# polarshield3_0f.net
KiCad netlist of a schematic drawn in EAGLE
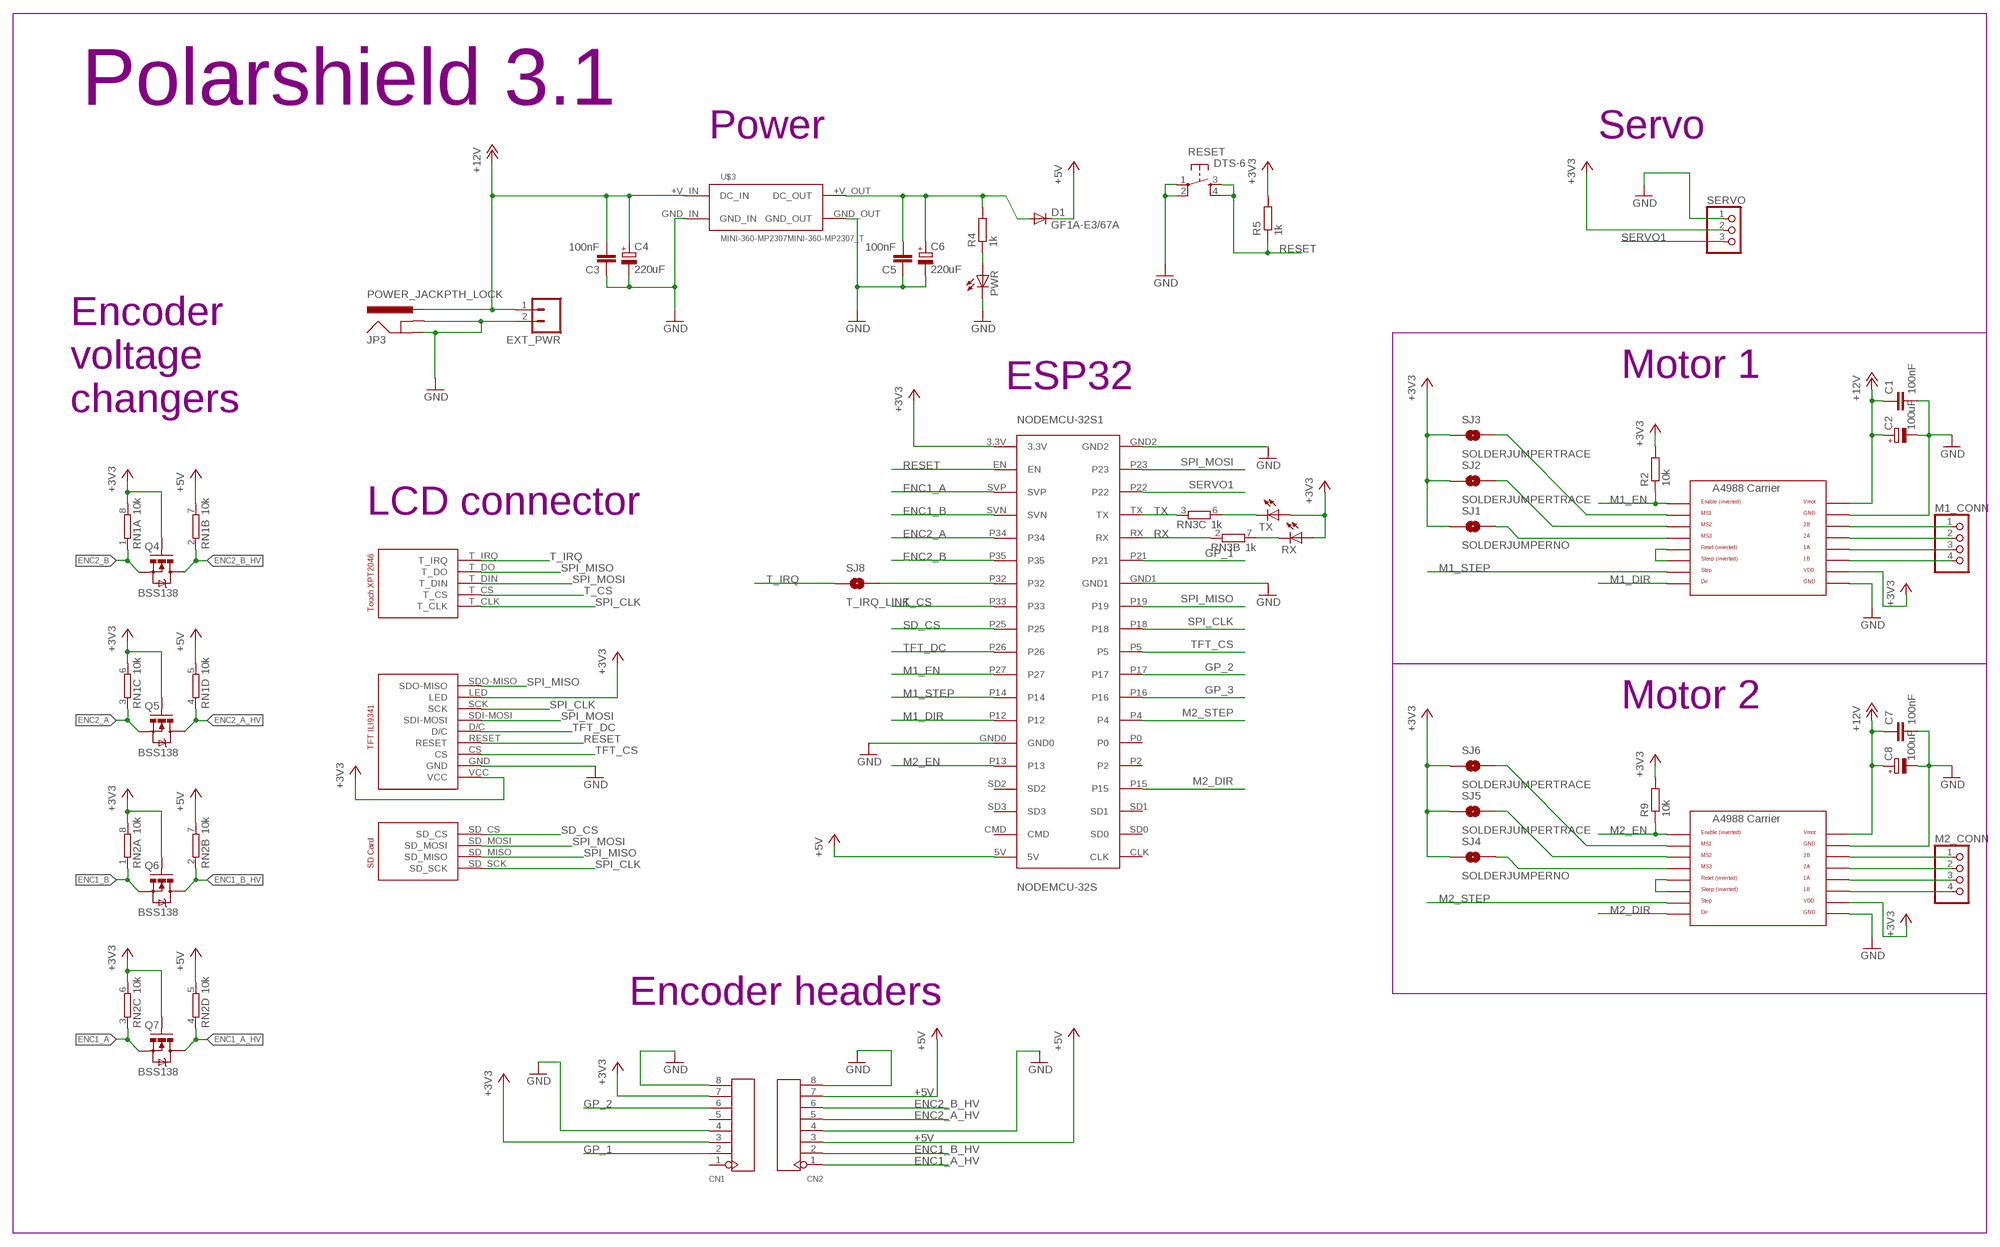
[diagram p0: schematic, sheet 1]

(export (version "E")
  (design (tool "Eeschema 10.0.6"))
  (components
    (comp (ref "C1")
      (value "100nF")
      (footprint "eagle-import:C0805")
      (libsource (lib "eagle-import") (part "C-EUC0805"))
    )
    (comp (ref "C2")
      (value "100uF")
      (footprint "eagle-import:153CLV-0605")
      (libsource (lib "eagle-import") (part "CPOL-EU153CLV-0605"))
    )
    (comp (ref "C3")
      (value "100nF")
      (footprint "eagle-import:C0805")
      (libsource (lib "eagle-import") (part "C-EUC0805"))
    )
    (comp (ref "C4")
      (value "220uF")
      (footprint "eagle-import:153CLV-0605")
      (libsource (lib "eagle-import") (part "CPOL-EU153CLV-0605"))
    )
    (comp (ref "C5")
      (value "100nF")
      (footprint "eagle-import:C0805")
      (libsource (lib "eagle-import") (part "C-EUC0805"))
    )
    (comp (ref "C6")
      (value "220uF")
      (footprint "eagle-import:153CLV-0605")
      (libsource (lib "eagle-import") (part "CPOL-EU153CLV-0605"))
    )
    (comp (ref "C7")
      (value "100nF")
      (footprint "eagle-import:C0805")
      (libsource (lib "eagle-import") (part "C-EUC0805"))
    )
    (comp (ref "C8")
      (value "100uF")
      (footprint "eagle-import:153CLV-0605")
      (libsource (lib "eagle-import") (part "CPOL-EU153CLV-0605"))
    )
    (comp (ref "CN1")
      (value "DIP-BLACK-FEMALE-HEADER-VERT(8P-2.54)")
      (footprint "eagle-import:H8-2.54")
      (fields (field (name "MPN") "F185-1108A1BSYC1"))
      (libsource (lib "eagle-import") (part "DIP-BLACK-FEMALE-HEADER-VERT(8P-2.54)"))
    )
    (comp (ref "CN2")
      (value "DIP-BLACK-FEMALE-HEADER-VERT(8P-2.54)")
      (footprint "eagle-import:H8-2.54")
      (fields (field (name "MPN") "F185-1108A1BSYC1"))
      (libsource (lib "eagle-import") (part "DIP-BLACK-FEMALE-HEADER-VERT(8P-2.54)"))
    )
    (comp (ref "D1")
      (value "GF1A-E3/67A")
      (footprint "eagle-import:DO214BA")
      (libsource (lib "eagle-import") (part "DIODE-DO214BA"))
    )
    (comp (ref "EXT_PWR")
      (value "M02PTH")
      (footprint "eagle-import:1X02")
      (libsource (lib "eagle-import") (part "M02PTH"))
    )
    (comp (ref "JP3")
      (value "POWER_JACKPTH_LOCK")
      (footprint "eagle-import:POWER_JACK_PTH_LOCK")
      (libsource (lib "eagle-import") (part "POWER_JACKPTH_LOCK"))
    )
    (comp (ref "M1_CONN")
      (value "PINHD-1X4/90")
      (footprint "eagle-import:1X04_90")
      (libsource (lib "eagle-import") (part "PINHD-1X4/90"))
    )
    (comp (ref "M2_CONN")
      (value "PINHD-1X4/90")
      (footprint "eagle-import:1X04_90")
      (libsource (lib "eagle-import") (part "PINHD-1X4/90"))
    )
    (comp (ref "MOTOR_1")
      (value "A4988BREAKOUT")
      (footprint "eagle-import:A4988BREAKOUT")
      (libsource (lib "eagle-import") (part "A4988BREAKOUT"))
    )
    (comp (ref "MOTOR_2")
      (value "A4988BREAKOUT")
      (footprint "eagle-import:A4988BREAKOUT")
      (libsource (lib "eagle-import") (part "A4988BREAKOUT"))
    )
    (comp (ref "NODEMCU-32S1")
      (value "NODEMCU-32S")
      (footprint "eagle-import:NODEMCU-32S")
      (libsource (lib "eagle-import") (part "NODEMCU-32S"))
    )
    (comp (ref "PWR")
      (value "LEDCHIPLED_0805")
      (footprint "eagle-import:CHIPLED_0805")
      (libsource (lib "eagle-import") (part "LEDCHIPLED_0805"))
    )
    (comp (ref "Q4")
      (value "BSS138")
      (footprint "eagle-import:SOT23-3")
      (libsource (lib "eagle-import") (part "MOSFET-NCHANNELSMD"))
    )
    (comp (ref "Q5")
      (value "BSS138")
      (footprint "eagle-import:SOT23-3")
      (libsource (lib "eagle-import") (part "MOSFET-NCHANNELSMD"))
    )
    (comp (ref "Q6")
      (value "BSS138")
      (footprint "eagle-import:SOT23-3")
      (libsource (lib "eagle-import") (part "MOSFET-NCHANNELSMD"))
    )
    (comp (ref "Q7")
      (value "BSS138")
      (footprint "eagle-import:SOT23-3")
      (libsource (lib "eagle-import") (part "MOSFET-NCHANNELSMD"))
    )
    (comp (ref "R2")
      (value "10k")
      (footprint "eagle-import:M0805")
      (libsource (lib "eagle-import") (part "R-EU_M0805"))
    )
    (comp (ref "R4")
      (value "1k")
      (footprint "eagle-import:M0805")
      (libsource (lib "eagle-import") (part "R-EU_M0805"))
    )
    (comp (ref "R5")
      (value "1k")
      (footprint "eagle-import:M0805")
      (libsource (lib "eagle-import") (part "R-EU_M0805"))
    )
    (comp (ref "R9")
      (value "10k")
      (footprint "eagle-import:M0805")
      (libsource (lib "eagle-import") (part "R-EU_M0805"))
    )
    (comp (ref "RESET")
      (value "DTS-6")
      (footprint "eagle-import:DTS-6")
      (libsource (lib "eagle-import") (part "DTS-6"))
    )
    (comp (ref "RN1")
      (value "10k")
      (footprint "eagle-import:EXB38V")
      (libsource (lib "eagle-import") (part "4R-NEXB38V"))
    )
    (comp (ref "RN2")
      (value "10k")
      (footprint "eagle-import:EXB38V")
      (libsource (lib "eagle-import") (part "4R-NEXB38V"))
    )
    (comp (ref "RN3")
      (value "1k")
      (footprint "eagle-import:EXB38V")
      (libsource (lib "eagle-import") (part "4R-NEXB38V"))
    )
    (comp (ref "RX")
      (value "LEDCHIPLED_0805")
      (footprint "eagle-import:CHIPLED_0805")
      (libsource (lib "eagle-import") (part "LEDCHIPLED_0805"))
    )
    (comp (ref "SERVO")
      (value "PINHD-1X3/90")
      (footprint "eagle-import:1X03_90")
      (libsource (lib "eagle-import") (part "PINHD-1X3/90"))
    )
    (comp (ref "SJ1")
      (value "SOLDERJUMPERNO")
      (footprint "eagle-import:SJ_2S-NO")
      (libsource (lib "eagle-import") (part "polargraph3_SOLDERJUMPERNO"))
    )
    (comp (ref "SJ2")
      (value "SOLDERJUMPERTRACE")
      (footprint "eagle-import:SJ_2S-TRACE")
      (libsource (lib "eagle-import") (part "polargraph3_SOLDERJUMPERTRACE"))
    )
    (comp (ref "SJ3")
      (value "SOLDERJUMPERTRACE")
      (footprint "eagle-import:SJ_2S-TRACE")
      (libsource (lib "eagle-import") (part "polargraph3_SOLDERJUMPERTRACE"))
    )
    (comp (ref "SJ4")
      (value "SOLDERJUMPERNO")
      (footprint "eagle-import:SJ_2S-NO")
      (libsource (lib "eagle-import") (part "polargraph3_SOLDERJUMPERNO"))
    )
    (comp (ref "SJ5")
      (value "SOLDERJUMPERTRACE")
      (footprint "eagle-import:SJ_2S-TRACE")
      (libsource (lib "eagle-import") (part "polargraph3_SOLDERJUMPERTRACE"))
    )
    (comp (ref "SJ6")
      (value "SOLDERJUMPERTRACE")
      (footprint "eagle-import:SJ_2S-TRACE")
      (libsource (lib "eagle-import") (part "polargraph3_SOLDERJUMPERTRACE"))
    )
    (comp (ref "SJ8")
      (value "T_IRQ_LINK")
      (footprint "eagle-import:SJ_2S-NO")
      (libsource (lib "eagle-import") (part "SOLDERJUMPERNO"))
    )
    (comp (ref "TX")
      (value "LEDCHIPLED_0805")
      (footprint "eagle-import:CHIPLED_0805")
      (libsource (lib "eagle-import") (part "LEDCHIPLED_0805"))
    )
    (comp (ref "U$2")
      (value "2.4_TFT_SPI_TOUCH_SD")
      (footprint "eagle-import:2.4_TFT_SPI_TOUCH_SD")
      (libsource (lib "eagle-import") (part "2.4_TFT_SPI_TOUCH_SD"))
    )
    (comp (ref "U$3")
      (value "MINI-360-MP2307MINI-360-MP2307_T")
      (footprint "eagle-import:MINI-360-MP2307")
      (libsource (lib "eagle-import") (part "MINI-360-MP2307MINI-360-MP2307_T"))
    )
  )
  (nets
    (net (code "1") (name "+3V3") (class "Default")
      (node (ref "CN1") (pin "3") (pinfunction "3_3") (pintype "bidirectional"))
      (node (ref "CN1") (pin "7") (pinfunction "7_7") (pintype "bidirectional"))
      (node (ref "MOTOR_1") (pin "VDD") (pinfunction "VDD_VDD") (pintype "power_in"))
      (node (ref "MOTOR_2") (pin "VDD") (pinfunction "VDD_VDD") (pintype "power_in"))
      (node (ref "NODEMCU-32S1") (pin "3.3V") (pinfunction "3.3V_3.3V") (pintype "bidirectional"))
      (node (ref "Q4") (pin "1") (pinfunction "G_1") (pintype "passive"))
      (node (ref "Q5") (pin "1") (pinfunction "G_1") (pintype "passive"))
      (node (ref "Q6") (pin "1") (pinfunction "G_1") (pintype "passive"))
      (node (ref "Q7") (pin "1") (pinfunction "G_1") (pintype "passive"))
      (node (ref "R2") (pin "2") (pinfunction "2_2") (pintype "passive"))
      (node (ref "R5") (pin "2") (pinfunction "2_2") (pintype "passive"))
      (node (ref "R9") (pin "2") (pinfunction "2_2") (pintype "passive"))
      (node (ref "RN1") (pin "6") (pinfunction "2_6") (pintype "passive"))
      (node (ref "RN1") (pin "8") (pinfunction "2_8") (pintype "passive"))
      (node (ref "RN2") (pin "6") (pinfunction "2_6") (pintype "passive"))
      (node (ref "RN2") (pin "8") (pinfunction "2_8") (pintype "passive"))
      (node (ref "RX") (pin "A") (pinfunction "A_A") (pintype "passive"))
      (node (ref "SERVO") (pin "2") (pinfunction "2_2") (pintype "passive"))
      (node (ref "SJ1") (pin "1") (pinfunction "1_1") (pintype "passive"))
      (node (ref "SJ2") (pin "1") (pinfunction "1_1") (pintype "passive"))
      (node (ref "SJ3") (pin "1") (pinfunction "1_1") (pintype "passive"))
      (node (ref "SJ4") (pin "1") (pinfunction "1_1") (pintype "passive"))
      (node (ref "SJ5") (pin "1") (pinfunction "1_1") (pintype "passive"))
      (node (ref "SJ6") (pin "1") (pinfunction "1_1") (pintype "passive"))
      (node (ref "TX") (pin "A") (pinfunction "A_A") (pintype "passive"))
      (node (ref "U$2") (pin "LED") (pinfunction "LED_LED") (pintype "bidirectional"))
      (node (ref "U$2") (pin "VCC") (pinfunction "VCC_VCC") (pintype "bidirectional"))
    )
    (net (code "2") (name "+5V") (class "Default")
      (node (ref "CN2") (pin "3") (pinfunction "3_3") (pintype "bidirectional"))
      (node (ref "CN2") (pin "7") (pinfunction "7_7") (pintype "bidirectional"))
      (node (ref "D1") (pin "C") (pinfunction "C_C") (pintype "passive"))
      (node (ref "NODEMCU-32S1") (pin "5V") (pinfunction "5V_5V") (pintype "bidirectional"))
      (node (ref "RN1") (pin "5") (pinfunction "2_5") (pintype "passive"))
      (node (ref "RN1") (pin "7") (pinfunction "2_7") (pintype "passive"))
      (node (ref "RN2") (pin "5") (pinfunction "2_5") (pintype "passive"))
      (node (ref "RN2") (pin "7") (pinfunction "2_7") (pintype "passive"))
    )
    (net (code "3") (name "+12V") (class "Default")
      (node (ref "C1") (pin "1") (pinfunction "1_1") (pintype "passive"))
      (node (ref "C2") (pin "+") (pinfunction "+_+") (pintype "passive"))
      (node (ref "C3") (pin "2") (pinfunction "2_2") (pintype "passive"))
      (node (ref "C4") (pin "+") (pinfunction "+_+") (pintype "passive"))
      (node (ref "C7") (pin "1") (pinfunction "1_1") (pintype "passive"))
      (node (ref "C8") (pin "+") (pinfunction "+_+") (pintype "passive"))
      (node (ref "EXT_PWR") (pin "1") (pinfunction "1_1") (pintype "passive"))
      (node (ref "JP3") (pin "PWR") (pinfunction "PWR_PWR") (pintype "bidirectional"))
      (node (ref "MOTOR_1") (pin "VMOT") (pinfunction "VMOT_VMOT") (pintype "power_in"))
      (node (ref "MOTOR_2") (pin "VMOT") (pinfunction "VMOT_VMOT") (pintype "power_in"))
      (node (ref "U$3") (pin "+V_IN") (pinfunction "DC_IN_+V_IN") (pintype "bidirectional"))
    )
    (net (code "4") (name "/GP_1") (class "Default")
      (node (ref "CN1") (pin "2") (pinfunction "2_2") (pintype "bidirectional"))
      (node (ref "NODEMCU-32S1") (pin "P21") (pinfunction "P21_P21") (pintype "bidirectional"))
    )
    (net (code "5") (name "/GP_2") (class "Default")
      (node (ref "CN1") (pin "6") (pinfunction "6_6") (pintype "bidirectional"))
      (node (ref "NODEMCU-32S1") (pin "P17") (pinfunction "P17_P17") (pintype "bidirectional"))
    )
    (net (code "6") (name "/GP_3") (class "Default")
      (node (ref "NODEMCU-32S1") (pin "P16") (pinfunction "P16_P16") (pintype "bidirectional"))
    )
    (net (code "7") (name "/M1_DIR") (class "Default")
      (node (ref "MOTOR_1") (pin "DIR") (pinfunction "DIR_DIR") (pintype "input"))
      (node (ref "NODEMCU-32S1") (pin "P12") (pinfunction "P12_P12") (pintype "bidirectional"))
    )
    (net (code "8") (name "/M1_EN") (class "Default")
      (node (ref "MOTOR_1") (pin "EN") (pinfunction "EN_EN") (pintype "input"))
      (node (ref "NODEMCU-32S1") (pin "P27") (pinfunction "P27_P27") (pintype "bidirectional"))
      (node (ref "R2") (pin "1") (pinfunction "1_1") (pintype "passive"))
    )
    (net (code "9") (name "/M1_STEP") (class "Default")
      (node (ref "MOTOR_1") (pin "STEP") (pinfunction "STEP_STEP") (pintype "input"))
      (node (ref "NODEMCU-32S1") (pin "P14") (pinfunction "P14_P14") (pintype "bidirectional"))
    )
    (net (code "10") (name "/M2_DIR") (class "Default")
      (node (ref "MOTOR_2") (pin "DIR") (pinfunction "DIR_DIR") (pintype "input"))
      (node (ref "NODEMCU-32S1") (pin "P15") (pinfunction "P15_P15") (pintype "bidirectional"))
    )
    (net (code "11") (name "/M2_EN") (class "Default")
      (node (ref "MOTOR_2") (pin "EN") (pinfunction "EN_EN") (pintype "input"))
      (node (ref "NODEMCU-32S1") (pin "P13") (pinfunction "P13_P13") (pintype "bidirectional"))
      (node (ref "R9") (pin "1") (pinfunction "1_1") (pintype "passive"))
    )
    (net (code "12") (name "/M2_STEP") (class "Default")
      (node (ref "MOTOR_2") (pin "STEP") (pinfunction "STEP_STEP") (pintype "input"))
      (node (ref "NODEMCU-32S1") (pin "P4") (pinfunction "P4_P4") (pintype "bidirectional"))
    )
    (net (code "13") (name "/RESET") (class "Default")
      (node (ref "NODEMCU-32S1") (pin "EN") (pinfunction "EN_EN") (pintype "bidirectional"))
      (node (ref "R5") (pin "1") (pinfunction "1_1") (pintype "passive"))
      (node (ref "RESET") (pin "3") (pinfunction "3_3") (pintype "passive"))
      (node (ref "RESET") (pin "4") (pinfunction "4_4") (pintype "passive"))
      (node (ref "U$2") (pin "RESET") (pinfunction "RESET_RESET") (pintype "bidirectional"))
    )
    (net (code "14") (name "/RX") (class "Default")
      (node (ref "NODEMCU-32S1") (pin "RX") (pinfunction "RX_RX") (pintype "bidirectional"))
      (node (ref "RN3") (pin "2") (pinfunction "1_2") (pintype "passive"))
    )
    (net (code "15") (name "/SD_CS") (class "Default")
      (node (ref "NODEMCU-32S1") (pin "P25") (pinfunction "P25_P25") (pintype "bidirectional"))
      (node (ref "U$2") (pin "SD_CS") (pinfunction "SD_CS_SD_CS") (pintype "bidirectional"))
    )
    (net (code "16") (name "/SERVO1") (class "Default")
      (node (ref "NODEMCU-32S1") (pin "P22") (pinfunction "P22_P22") (pintype "bidirectional"))
      (node (ref "SERVO") (pin "3") (pinfunction "3_3") (pintype "passive"))
    )
    (net (code "17") (name "/SPI_CLK") (class "Default")
      (node (ref "NODEMCU-32S1") (pin "P18") (pinfunction "P18_P18") (pintype "bidirectional"))
      (node (ref "U$2") (pin "SCK") (pinfunction "SCK_SCK") (pintype "bidirectional"))
      (node (ref "U$2") (pin "SD_SCK") (pinfunction "SD_SCK_SD_SCK") (pintype "bidirectional"))
      (node (ref "U$2") (pin "T_CLK") (pinfunction "T_CLK_T_CLK") (pintype "input"))
    )
    (net (code "18") (name "/SPI_MISO") (class "Default")
      (node (ref "NODEMCU-32S1") (pin "P19") (pinfunction "P19_P19") (pintype "bidirectional"))
      (node (ref "U$2") (pin "SDO-MISO") (pinfunction "SDO-MISO_SDO-MISO") (pintype "bidirectional"))
      (node (ref "U$2") (pin "SD_MISO") (pinfunction "SD_MISO_SD_MISO") (pintype "bidirectional"))
      (node (ref "U$2") (pin "T_DO") (pinfunction "T_DO_T_DO") (pintype "output"))
    )
    (net (code "19") (name "/SPI_MOSI") (class "Default")
      (node (ref "NODEMCU-32S1") (pin "P23") (pinfunction "P23_P23") (pintype "bidirectional"))
      (node (ref "U$2") (pin "SDI-MOSI") (pinfunction "SDI-MOSI_SDI-MOSI") (pintype "bidirectional"))
      (node (ref "U$2") (pin "SD_MOSI") (pinfunction "SD_MOSI_SD_MOSI") (pintype "bidirectional"))
      (node (ref "U$2") (pin "T_DIN") (pinfunction "T_DIN_T_DIN") (pintype "input"))
    )
    (net (code "20") (name "/TFT_CS") (class "Default")
      (node (ref "NODEMCU-32S1") (pin "P5") (pinfunction "P5_P5") (pintype "bidirectional"))
      (node (ref "U$2") (pin "CS") (pinfunction "CS_CS") (pintype "bidirectional"))
    )
    (net (code "21") (name "/TFT_DC") (class "Default")
      (node (ref "NODEMCU-32S1") (pin "P26") (pinfunction "P26_P26") (pintype "bidirectional"))
      (node (ref "U$2") (pin "D/C") (pinfunction "D/C_D/C") (pintype "bidirectional"))
    )
    (net (code "22") (name "/TX") (class "Default")
      (node (ref "NODEMCU-32S1") (pin "TX") (pinfunction "TX_TX") (pintype "bidirectional"))
      (node (ref "RN3") (pin "3") (pinfunction "1_3") (pintype "passive"))
    )
    (net (code "23") (name "/T_CS") (class "Default")
      (node (ref "NODEMCU-32S1") (pin "P33") (pinfunction "P33_P33") (pintype "bidirectional"))
      (node (ref "U$2") (pin "T_CS") (pinfunction "T_CS_T_CS") (pintype "output"))
    )
    (net (code "24") (name "/T_IRQ") (class "Default")
      (node (ref "SJ8") (pin "1") (pinfunction "1_1") (pintype "passive"))
      (node (ref "U$2") (pin "T_IRQ") (pinfunction "T_IRQ_T_IRQ") (pintype "output"))
    )
    (net (code "25") (name "ENC1_A") (class "Default")
      (node (ref "NODEMCU-32S1") (pin "SVP") (pinfunction "SVP_SVP") (pintype "bidirectional"))
      (node (ref "Q7") (pin "2") (pinfunction "S_2") (pintype "passive"))
      (node (ref "RN2") (pin "3") (pinfunction "1_3") (pintype "passive"))
    )
    (net (code "26") (name "ENC1_A_HV") (class "Default")
      (node (ref "CN2") (pin "1") (pinfunction "1_1") (pintype "bidirectional"))
      (node (ref "Q7") (pin "3") (pinfunction "D_3") (pintype "passive"))
      (node (ref "RN2") (pin "4") (pinfunction "1_4") (pintype "passive"))
    )
    (net (code "27") (name "ENC1_B") (class "Default")
      (node (ref "NODEMCU-32S1") (pin "SVN") (pinfunction "SVN_SVN") (pintype "bidirectional"))
      (node (ref "Q6") (pin "2") (pinfunction "S_2") (pintype "passive"))
      (node (ref "RN2") (pin "1") (pinfunction "1_1") (pintype "passive"))
    )
    (net (code "28") (name "ENC1_B_HV") (class "Default")
      (node (ref "CN2") (pin "2") (pinfunction "2_2") (pintype "bidirectional"))
      (node (ref "Q6") (pin "3") (pinfunction "D_3") (pintype "passive"))
      (node (ref "RN2") (pin "2") (pinfunction "1_2") (pintype "passive"))
    )
    (net (code "29") (name "ENC2_A") (class "Default")
      (node (ref "NODEMCU-32S1") (pin "P34") (pinfunction "P34_P34") (pintype "bidirectional"))
      (node (ref "Q5") (pin "2") (pinfunction "S_2") (pintype "passive"))
      (node (ref "RN1") (pin "3") (pinfunction "1_3") (pintype "passive"))
    )
    (net (code "30") (name "ENC2_A_HV") (class "Default")
      (node (ref "CN2") (pin "5") (pinfunction "5_5") (pintype "bidirectional"))
      (node (ref "Q5") (pin "3") (pinfunction "D_3") (pintype "passive"))
      (node (ref "RN1") (pin "4") (pinfunction "1_4") (pintype "passive"))
    )
    (net (code "31") (name "ENC2_B") (class "Default")
      (node (ref "NODEMCU-32S1") (pin "P35") (pinfunction "P35_P35") (pintype "bidirectional"))
      (node (ref "Q4") (pin "2") (pinfunction "S_2") (pintype "passive"))
      (node (ref "RN1") (pin "1") (pinfunction "1_1") (pintype "passive"))
    )
    (net (code "32") (name "ENC2_B_HV") (class "Default")
      (node (ref "CN2") (pin "6") (pinfunction "6_6") (pintype "bidirectional"))
      (node (ref "Q4") (pin "3") (pinfunction "D_3") (pintype "passive"))
      (node (ref "RN1") (pin "2") (pinfunction "1_2") (pintype "passive"))
    )
    (net (code "33") (name "GND") (class "Default")
      (node (ref "C1") (pin "2") (pinfunction "2_2") (pintype "passive"))
      (node (ref "C2") (pin "-") (pinfunction "-_-") (pintype "passive"))
      (node (ref "C3") (pin "1") (pinfunction "1_1") (pintype "passive"))
      (node (ref "C4") (pin "-") (pinfunction "-_-") (pintype "passive"))
      (node (ref "C5") (pin "1") (pinfunction "1_1") (pintype "passive"))
      (node (ref "C6") (pin "-") (pinfunction "-_-") (pintype "passive"))
      (node (ref "C7") (pin "2") (pinfunction "2_2") (pintype "passive"))
      (node (ref "C8") (pin "-") (pinfunction "-_-") (pintype "passive"))
      (node (ref "CN1") (pin "4") (pinfunction "4_4") (pintype "bidirectional"))
      (node (ref "CN1") (pin "8") (pinfunction "8_8") (pintype "bidirectional"))
      (node (ref "CN2") (pin "4") (pinfunction "4_4") (pintype "bidirectional"))
      (node (ref "CN2") (pin "8") (pinfunction "8_8") (pintype "bidirectional"))
      (node (ref "EXT_PWR") (pin "2") (pinfunction "2_2") (pintype "passive"))
      (node (ref "JP3") (pin "GND") (pinfunction "GND_GND") (pintype "bidirectional"))
      (node (ref "JP3") (pin "GNDBREAK") (pinfunction "GNDBREAK_GNDBREAK") (pintype "bidirectional"))
      (node (ref "MOTOR_1") (pin "GND") (pinfunction "GND_GND") (pintype "power_in"))
      (node (ref "MOTOR_1") (pin "GND@0") (pinfunction "GND_GND@0") (pintype "power_in"))
      (node (ref "MOTOR_2") (pin "GND") (pinfunction "GND_GND") (pintype "power_in"))
      (node (ref "MOTOR_2") (pin "GND@0") (pinfunction "GND_GND@0") (pintype "power_in"))
      (node (ref "NODEMCU-32S1") (pin "GND0") (pinfunction "GND0_GND0") (pintype "bidirectional"))
      (node (ref "NODEMCU-32S1") (pin "GND1") (pinfunction "GND1_GND1") (pintype "bidirectional"))
      (node (ref "NODEMCU-32S1") (pin "GND2") (pinfunction "GND2_GND2") (pintype "bidirectional"))
      (node (ref "PWR") (pin "C") (pinfunction "C_C") (pintype "passive"))
      (node (ref "RESET") (pin "1") (pinfunction "1_1") (pintype "passive"))
      (node (ref "RESET") (pin "2") (pinfunction "2_2") (pintype "passive"))
      (node (ref "SERVO") (pin "1") (pinfunction "1_1") (pintype "passive"))
      (node (ref "U$2") (pin "GND") (pinfunction "GND_GND") (pintype "bidirectional"))
      (node (ref "U$3") (pin "GND_IN") (pinfunction "GND_IN_GND_IN") (pintype "bidirectional"))
      (node (ref "U$3") (pin "GND_OUT") (pinfunction "GND_OUT_GND_OUT") (pintype "bidirectional"))
    )
    (net (code "34") (name "Net-(M1_CONN-Pad1)") (class "Default")
      (node (ref "M1_CONN") (pin "1") (pinfunction "1_1") (pintype "passive"))
      (node (ref "MOTOR_1") (pin "2B") (pinfunction "2B_2B") (pintype "output"))
    )
    (net (code "35") (name "Net-(M1_CONN-Pad2)") (class "Default")
      (node (ref "M1_CONN") (pin "2") (pinfunction "2_2") (pintype "passive"))
      (node (ref "MOTOR_1") (pin "2A") (pinfunction "2A_2A") (pintype "output"))
    )
    (net (code "36") (name "Net-(M1_CONN-Pad3)") (class "Default")
      (node (ref "M1_CONN") (pin "3") (pinfunction "3_3") (pintype "passive"))
      (node (ref "MOTOR_1") (pin "1A") (pinfunction "1A_1A") (pintype "output"))
    )
    (net (code "37") (name "Net-(M1_CONN-Pad4)") (class "Default")
      (node (ref "M1_CONN") (pin "4") (pinfunction "4_4") (pintype "passive"))
      (node (ref "MOTOR_1") (pin "1B") (pinfunction "1B_1B") (pintype "output"))
    )
    (net (code "38") (name "Net-(M2_CONN-Pad1)") (class "Default")
      (node (ref "M2_CONN") (pin "1") (pinfunction "1_1") (pintype "passive"))
      (node (ref "MOTOR_2") (pin "2B") (pinfunction "2B_2B") (pintype "output"))
    )
    (net (code "39") (name "Net-(M2_CONN-Pad2)") (class "Default")
      (node (ref "M2_CONN") (pin "2") (pinfunction "2_2") (pintype "passive"))
      (node (ref "MOTOR_2") (pin "2A") (pinfunction "2A_2A") (pintype "output"))
    )
    (net (code "40") (name "Net-(M2_CONN-Pad3)") (class "Default")
      (node (ref "M2_CONN") (pin "3") (pinfunction "3_3") (pintype "passive"))
      (node (ref "MOTOR_2") (pin "1A") (pinfunction "1A_1A") (pintype "output"))
    )
    (net (code "41") (name "Net-(M2_CONN-Pad4)") (class "Default")
      (node (ref "M2_CONN") (pin "4") (pinfunction "4_4") (pintype "passive"))
      (node (ref "MOTOR_2") (pin "1B") (pinfunction "1B_1B") (pintype "output"))
    )
    (net (code "42") (name "Net-(MOTOR_1-PadMS1)") (class "Default")
      (node (ref "MOTOR_1") (pin "MS1") (pinfunction "MS1_MS1") (pintype "input"))
      (node (ref "SJ3") (pin "2") (pinfunction "2_2") (pintype "passive"))
    )
    (net (code "43") (name "Net-(MOTOR_1-PadMS2)") (class "Default")
      (node (ref "MOTOR_1") (pin "MS2") (pinfunction "MS2_MS2") (pintype "input"))
      (node (ref "SJ2") (pin "2") (pinfunction "2_2") (pintype "passive"))
    )
    (net (code "44") (name "Net-(MOTOR_1-PadMS3)") (class "Default")
      (node (ref "MOTOR_1") (pin "MS3") (pinfunction "MS3_MS3") (pintype "input"))
      (node (ref "SJ1") (pin "2") (pinfunction "2_2") (pintype "passive"))
    )
    (net (code "45") (name "Net-(MOTOR_1-SLEEP)") (class "Default")
      (node (ref "MOTOR_1") (pin "RST") (pinfunction "RST_RST") (pintype "input"))
      (node (ref "MOTOR_1") (pin "SLP") (pinfunction "SLEEP_SLP") (pintype "input"))
    )
    (net (code "46") (name "Net-(MOTOR_2-PadMS1)") (class "Default")
      (node (ref "MOTOR_2") (pin "MS1") (pinfunction "MS1_MS1") (pintype "input"))
      (node (ref "SJ6") (pin "2") (pinfunction "2_2") (pintype "passive"))
    )
    (net (code "47") (name "Net-(MOTOR_2-PadMS2)") (class "Default")
      (node (ref "MOTOR_2") (pin "MS2") (pinfunction "MS2_MS2") (pintype "input"))
      (node (ref "SJ5") (pin "2") (pinfunction "2_2") (pintype "passive"))
    )
    (net (code "48") (name "Net-(MOTOR_2-PadMS3)") (class "Default")
      (node (ref "MOTOR_2") (pin "MS3") (pinfunction "MS3_MS3") (pintype "input"))
      (node (ref "SJ4") (pin "2") (pinfunction "2_2") (pintype "passive"))
    )
    (net (code "49") (name "Net-(MOTOR_2-SLEEP)") (class "Default")
      (node (ref "MOTOR_2") (pin "RST") (pinfunction "RST_RST") (pintype "input"))
      (node (ref "MOTOR_2") (pin "SLP") (pinfunction "SLEEP_SLP") (pintype "input"))
    )
    (net (code "50") (name "Net-(NODEMCU-32S1-PadP32)") (class "Default")
      (node (ref "NODEMCU-32S1") (pin "P32") (pinfunction "P32_P32") (pintype "bidirectional"))
      (node (ref "SJ8") (pin "2") (pinfunction "2_2") (pintype "passive"))
    )
    (net (code "51") (name "Net-(PWR-PadA)") (class "Default")
      (node (ref "PWR") (pin "A") (pinfunction "A_A") (pintype "passive"))
      (node (ref "R4") (pin "1") (pinfunction "1_1") (pintype "passive"))
    )
    (net (code "52") (name "Net-(RN3B-2)") (class "Default")
      (node (ref "RN3") (pin "7") (pinfunction "2_7") (pintype "passive"))
      (node (ref "RX") (pin "C") (pinfunction "C_C") (pintype "passive"))
    )
    (net (code "53") (name "Net-(RN3C-2)") (class "Default")
      (node (ref "RN3") (pin "6") (pinfunction "2_6") (pintype "passive"))
      (node (ref "TX") (pin "C") (pinfunction "C_C") (pintype "passive"))
    )
    (net (code "54") (name "Net-(U$3-DC_OUT)") (class "Default")
      (node (ref "C5") (pin "2") (pinfunction "2_2") (pintype "passive"))
      (node (ref "C6") (pin "+") (pinfunction "+_+") (pintype "passive"))
      (node (ref "D1") (pin "A") (pinfunction "A_A") (pintype "passive"))
      (node (ref "R4") (pin "2") (pinfunction "2_2") (pintype "passive"))
      (node (ref "U$3") (pin "+V_OUT") (pinfunction "DC_OUT_+V_OUT") (pintype "bidirectional"))
    )
    (net (code "55") (name "unconnected-(CN1-Pad1)") (class "Default")
      (node (ref "CN1") (pin "1") (pinfunction "1_1") (pintype "bidirectional"))
    )
    (net (code "56") (name "unconnected-(CN1-Pad5)") (class "Default")
      (node (ref "CN1") (pin "5") (pinfunction "5_5") (pintype "bidirectional"))
    )
    (net (code "57") (name "unconnected-(NODEMCU-32S1-PadCLK)") (class "Default")
      (node (ref "NODEMCU-32S1") (pin "CLK") (pinfunction "CLK_CLK") (pintype "bidirectional"))
    )
    (net (code "58") (name "unconnected-(NODEMCU-32S1-PadCMD)") (class "Default")
      (node (ref "NODEMCU-32S1") (pin "CMD") (pinfunction "CMD_CMD") (pintype "bidirectional"))
    )
    (net (code "59") (name "unconnected-(NODEMCU-32S1-PadP0)") (class "Default")
      (node (ref "NODEMCU-32S1") (pin "P0") (pinfunction "P0_P0") (pintype "bidirectional"))
    )
    (net (code "60") (name "unconnected-(NODEMCU-32S1-PadP2)") (class "Default")
      (node (ref "NODEMCU-32S1") (pin "P2") (pinfunction "P2_P2") (pintype "bidirectional"))
    )
    (net (code "61") (name "unconnected-(NODEMCU-32S1-PadSD0)") (class "Default")
      (node (ref "NODEMCU-32S1") (pin "SD0") (pinfunction "SD0_SD0") (pintype "bidirectional"))
    )
    (net (code "62") (name "unconnected-(NODEMCU-32S1-PadSD1)") (class "Default")
      (node (ref "NODEMCU-32S1") (pin "SD1") (pinfunction "SD1_SD1") (pintype "bidirectional"))
    )
    (net (code "63") (name "unconnected-(NODEMCU-32S1-PadSD2)") (class "Default")
      (node (ref "NODEMCU-32S1") (pin "SD2") (pinfunction "SD2_SD2") (pintype "bidirectional"))
    )
    (net (code "64") (name "unconnected-(NODEMCU-32S1-PadSD3)") (class "Default")
      (node (ref "NODEMCU-32S1") (pin "SD3") (pinfunction "SD3_SD3") (pintype "bidirectional"))
    )
  )
)
